# SCH_Latencycam_2024-05-11.net
KiCad netlist of a schematic drawn in EasyEDA
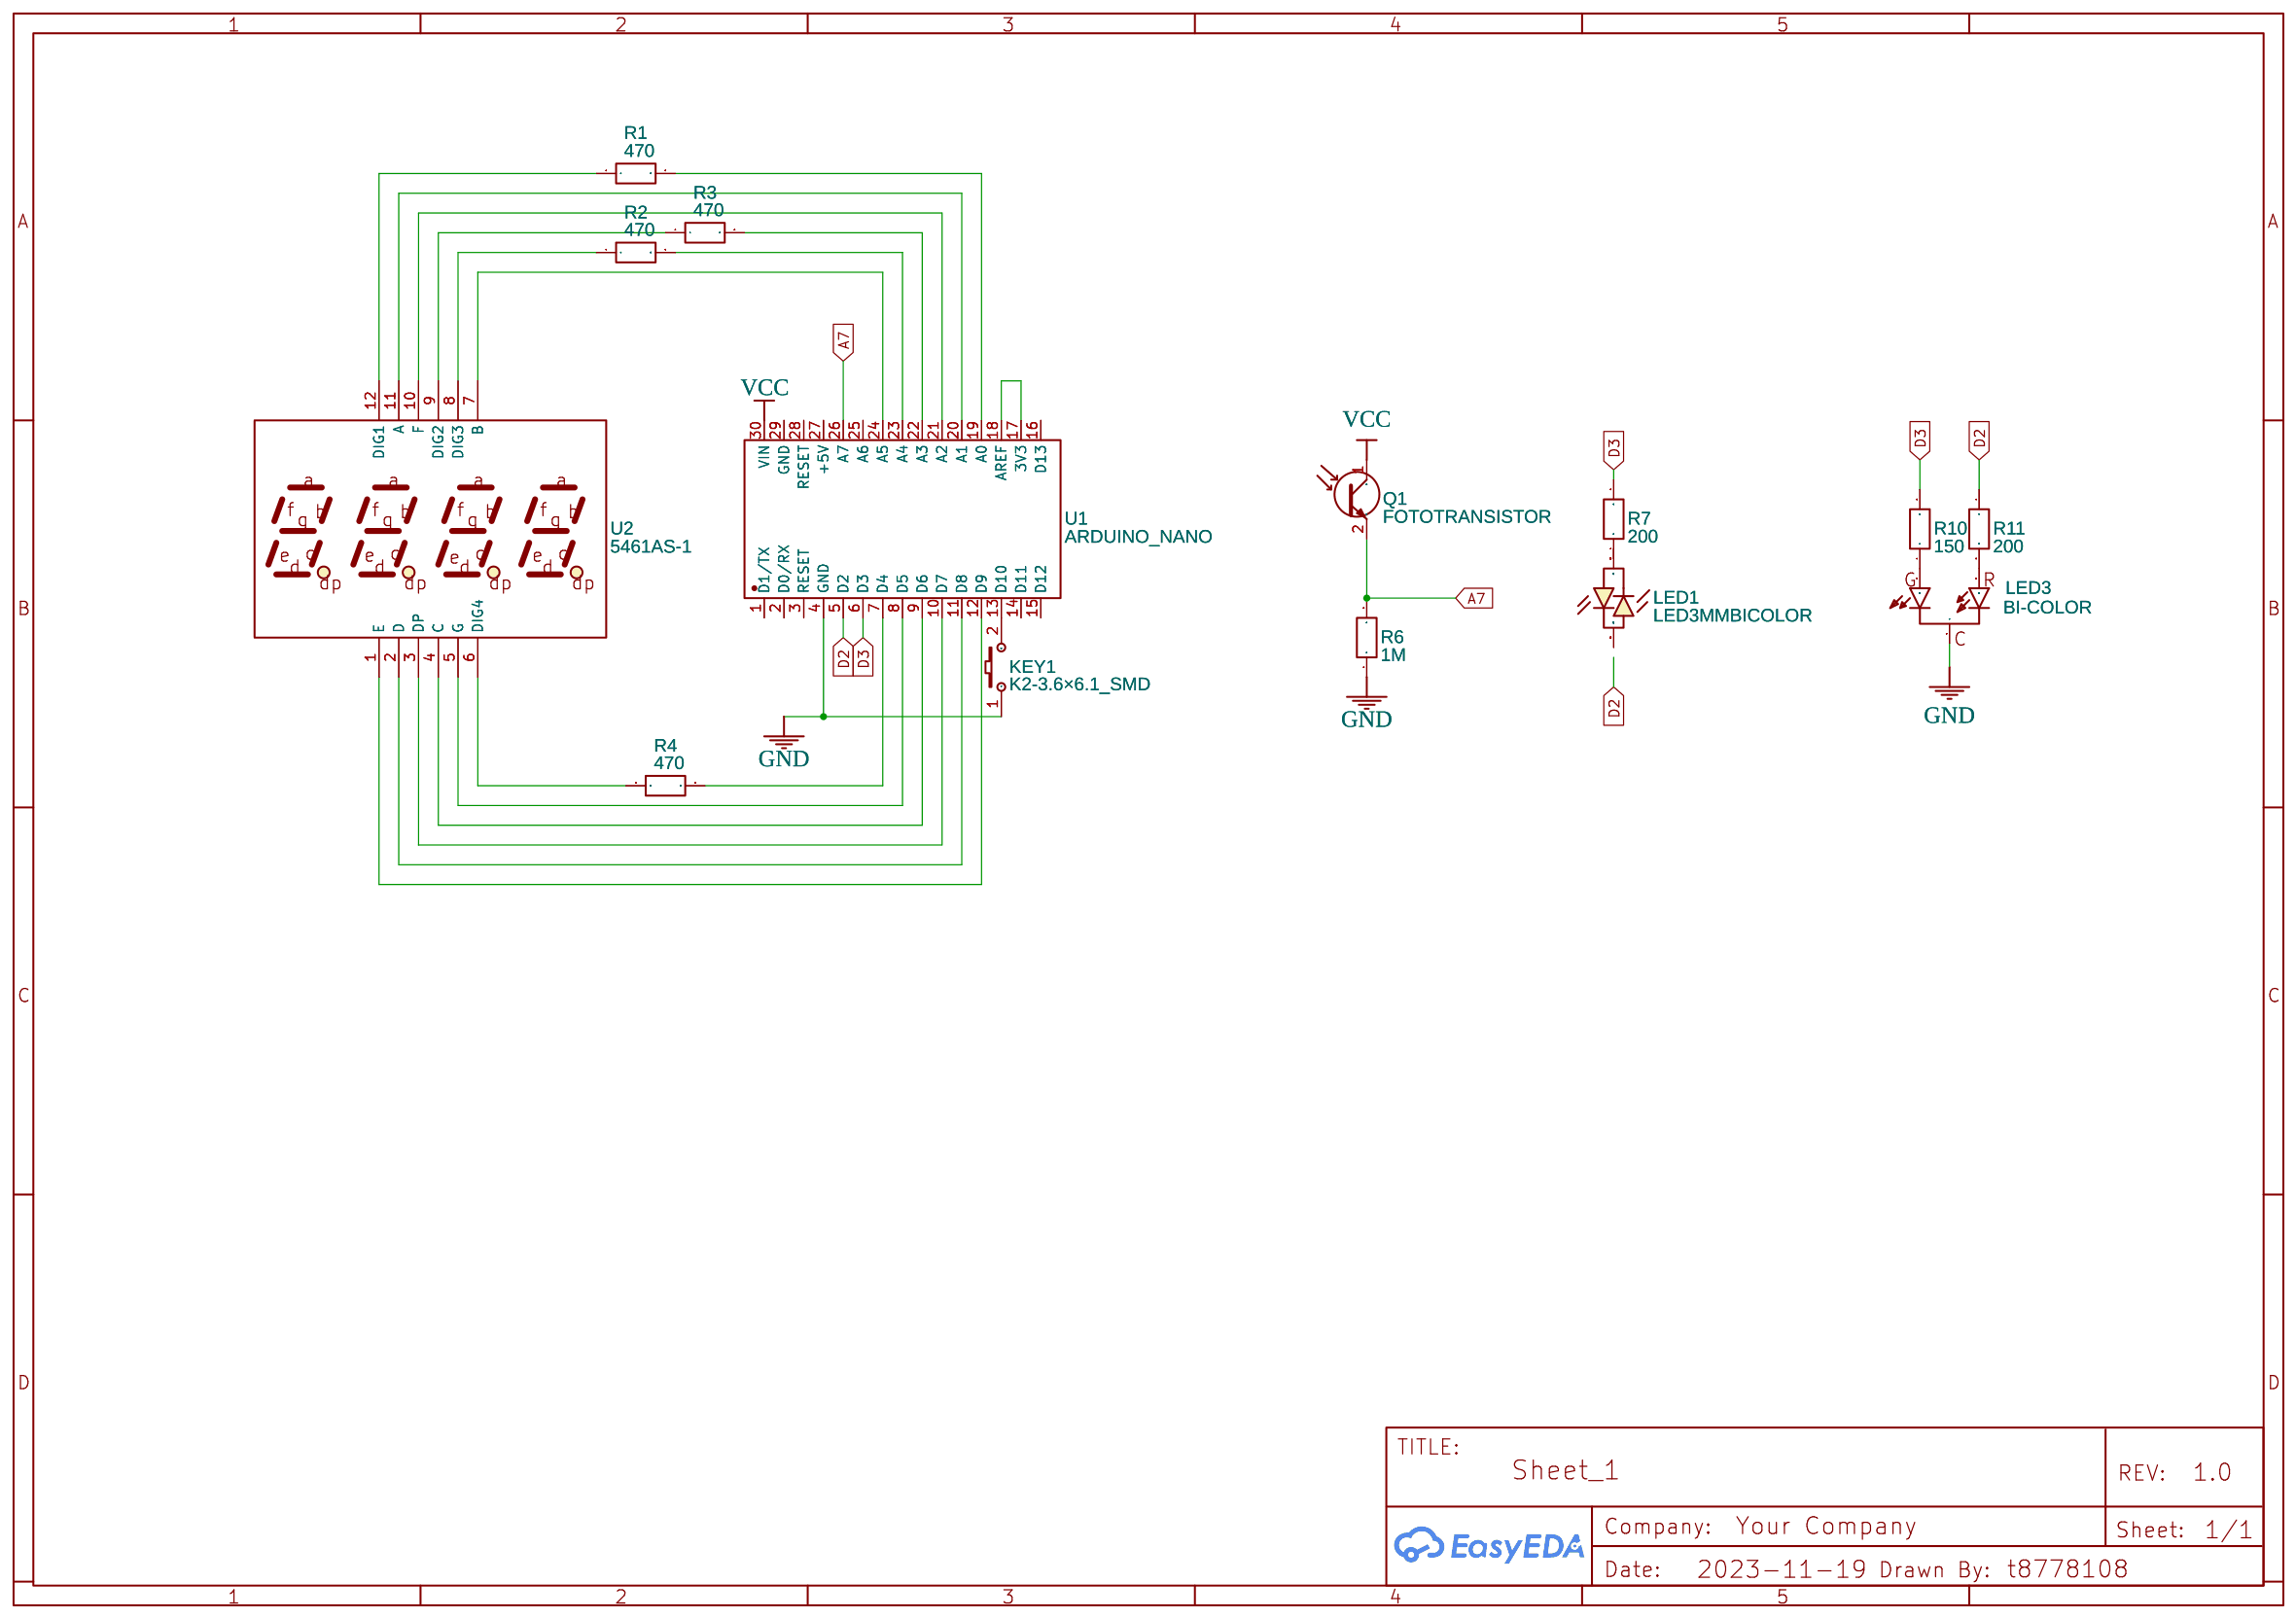
[diagram p0: schematic sheet]

(export (version "E")
  (design (tool "Eeschema 10.0.6"))
  (components
    (comp (ref "KEY1")
      (value "K2-3.6×6.1_SMD")
      (fields (field (name "Manufacturer Part") "K2-1107ST-A4SW-06"))
      (libsource (lib "") (part "K2-3.6×6.1_SMD"))
    )
    (comp (ref "LED1") (value "LED3MMBICOLOR") (libsource (lib "") (part "LED3MMBICOLOR")))
    (comp (ref "LED3") (value "BI-COLOR") (libsource (lib "") (part "BI-COLOR LED 5MM COMMON CATHODE COPY")))
    (comp (ref "Q1") (value "FOTOTRANSISTOR") (libsource (lib "") (part "FOTOTRANSISTOR")))
    (comp (ref "R1") (value "470") (libsource (lib "") (part "R_0603_EU")))
    (comp (ref "R2") (value "470") (libsource (lib "") (part "R_0603_EU")))
    (comp (ref "R3") (value "470") (libsource (lib "") (part "R_0603_EU")))
    (comp (ref "R4") (value "470") (libsource (lib "") (part "R_0603_EU")))
    (comp (ref "R6") (value "1M") (libsource (lib "") (part "R_0603_EU_1")))
    (comp (ref "R7") (value "200") (libsource (lib "") (part "R_0603_EU_1")))
    (comp (ref "R10") (value "150") (libsource (lib "") (part "R_0603_EU_1")))
    (comp (ref "R11") (value "200") (libsource (lib "") (part "R_0603_EU_2")))
    (comp (ref "U1") (value "ARDUINO_NANO") (libsource (lib "") (part "ARDUINO_NANO")))
    (comp (ref "U2") (value "5461AS-1") (libsource (lib "") (part "5461AS-1")))
  )
  (nets
    (net (code "1") (name "A7") (class "Default")
      (node (ref "Q1") (pin "2") (pinfunction "E_2") (pintype "unspecified"))
      (node (ref "R6") (pin "2") (pinfunction "2_2") (pintype "unspecified"))
      (node (ref "U1") (pin "26") (pinfunction "A7_26") (pintype "unspecified"))
    )
    (net (code "2") (name "D2") (class "Default")
      (node (ref "R11") (pin "1") (pinfunction "1_1") (pintype "unspecified"))
      (node (ref "U1") (pin "5") (pinfunction "D2_5") (pintype "unspecified"))
    )
    (net (code "3") (name "D3") (class "Default")
      (node (ref "R10") (pin "2") (pinfunction "2_2") (pintype "unspecified"))
      (node (ref "R7") (pin "2") (pinfunction "2_2") (pintype "unspecified"))
      (node (ref "U1") (pin "6") (pinfunction "D3_6") (pintype "unspecified"))
    )
    (net (code "4") (name "GND") (class "Default")
      (node (ref "KEY1") (pin "1") (pinfunction "1_1") (pintype "unspecified"))
      (node (ref "LED3") (pin "2") (pinfunction "A_2") (pintype "unspecified"))
      (node (ref "R6") (pin "1") (pinfunction "1_1") (pintype "unspecified"))
      (node (ref "U1") (pin "4") (pinfunction "GND_4") (pintype "unspecified"))
    )
    (net (code "5") (name "Net-(LED1-PadAG-CR)") (class "Default")
      (node (ref "LED1") (pin "AG-CR") (pinfunction "AG-CR_AG-CR") (pintype "unspecified"))
      (node (ref "R7") (pin "1") (pinfunction "1_1") (pintype "unspecified"))
    )
    (net (code "6") (name "Net-(LED3-G)") (class "Default")
      (node (ref "LED3") (pin "1") (pinfunction "G_1") (pintype "unspecified"))
      (node (ref "R10") (pin "1") (pinfunction "1_1") (pintype "unspecified"))
    )
    (net (code "7") (name "Net-(LED3-R)") (class "Default")
      (node (ref "LED3") (pin "3") (pinfunction "R_3") (pintype "unspecified"))
      (node (ref "R11") (pin "2") (pinfunction "2_2") (pintype "unspecified"))
    )
    (net (code "8") (name "Net-(U1-3V3)") (class "Default")
      (node (ref "U1") (pin "17") (pinfunction "3V3_17") (pintype "unspecified"))
      (node (ref "U1") (pin "18") (pinfunction "AREF_18") (pintype "unspecified"))
    )
    (net (code "9") (name "Net-(U1-A0)") (class "Default")
      (node (ref "R1") (pin "2") (pinfunction "2_2") (pintype "unspecified"))
      (node (ref "U1") (pin "19") (pinfunction "A0_19") (pintype "unspecified"))
    )
    (net (code "10") (name "Net-(U1-A1)") (class "Default")
      (node (ref "U1") (pin "20") (pinfunction "A1_20") (pintype "unspecified"))
      (node (ref "U2") (pin "11") (pinfunction "A_11") (pintype "input"))
    )
    (net (code "11") (name "Net-(U1-A2)") (class "Default")
      (node (ref "U1") (pin "21") (pinfunction "A2_21") (pintype "unspecified"))
      (node (ref "U2") (pin "10") (pinfunction "F_10") (pintype "input"))
    )
    (net (code "12") (name "Net-(U1-A3)") (class "Default")
      (node (ref "R3") (pin "2") (pinfunction "2_2") (pintype "unspecified"))
      (node (ref "U1") (pin "22") (pinfunction "A3_22") (pintype "unspecified"))
    )
    (net (code "13") (name "Net-(U1-A4)") (class "Default")
      (node (ref "R2") (pin "2") (pinfunction "2_2") (pintype "unspecified"))
      (node (ref "U1") (pin "23") (pinfunction "A4_23") (pintype "unspecified"))
    )
    (net (code "14") (name "Net-(U1-A5)") (class "Default")
      (node (ref "U1") (pin "24") (pinfunction "A5_24") (pintype "unspecified"))
      (node (ref "U2") (pin "7") (pinfunction "B_7") (pintype "input"))
    )
    (net (code "15") (name "Net-(U1-D4)") (class "Default")
      (node (ref "R4") (pin "2") (pinfunction "2_2") (pintype "unspecified"))
      (node (ref "U1") (pin "7") (pinfunction "D4_7") (pintype "unspecified"))
    )
    (net (code "16") (name "Net-(U1-D5)") (class "Default")
      (node (ref "U1") (pin "8") (pinfunction "D5_8") (pintype "unspecified"))
      (node (ref "U2") (pin "5") (pinfunction "G_5") (pintype "input"))
    )
    (net (code "17") (name "Net-(U1-D6)") (class "Default")
      (node (ref "U1") (pin "9") (pinfunction "D6_9") (pintype "unspecified"))
      (node (ref "U2") (pin "4") (pinfunction "C_4") (pintype "input"))
    )
    (net (code "18") (name "Net-(U1-D7)") (class "Default")
      (node (ref "U1") (pin "10") (pinfunction "D7_10") (pintype "unspecified"))
      (node (ref "U2") (pin "3") (pinfunction "DP_3") (pintype "input"))
    )
    (net (code "19") (name "Net-(U1-D8)") (class "Default")
      (node (ref "U1") (pin "11") (pinfunction "D8_11") (pintype "unspecified"))
      (node (ref "U2") (pin "2") (pinfunction "D_2") (pintype "input"))
    )
    (net (code "20") (name "Net-(U1-D9)") (class "Default")
      (node (ref "U1") (pin "12") (pinfunction "D9_12") (pintype "unspecified"))
      (node (ref "U2") (pin "1") (pinfunction "E_1") (pintype "input"))
    )
    (net (code "21") (name "Net-(U1-D10)") (class "Default")
      (node (ref "KEY1") (pin "2") (pinfunction "2_2") (pintype "unspecified"))
      (node (ref "U1") (pin "13") (pinfunction "D10_13") (pintype "unspecified"))
    )
    (net (code "22") (name "Net-(U2-DIG1)") (class "Default")
      (node (ref "R1") (pin "1") (pinfunction "1_1") (pintype "unspecified"))
      (node (ref "U2") (pin "12") (pinfunction "DIG1_12") (pintype "input"))
    )
    (net (code "23") (name "Net-(U2-DIG2)") (class "Default")
      (node (ref "R3") (pin "1") (pinfunction "1_1") (pintype "unspecified"))
      (node (ref "U2") (pin "9") (pinfunction "DIG2_9") (pintype "input"))
    )
    (net (code "24") (name "Net-(U2-DIG3)") (class "Default")
      (node (ref "R2") (pin "1") (pinfunction "1_1") (pintype "unspecified"))
      (node (ref "U2") (pin "8") (pinfunction "DIG3_8") (pintype "input"))
    )
    (net (code "25") (name "Net-(U2-DIG4)") (class "Default")
      (node (ref "R4") (pin "1") (pinfunction "1_1") (pintype "unspecified"))
      (node (ref "U2") (pin "6") (pinfunction "DIG4_6") (pintype "input"))
    )
    (net (code "26") (name "VCC") (class "Default")
      (node (ref "Q1") (pin "1") (pinfunction "C_1") (pintype "unspecified"))
      (node (ref "U1") (pin "30") (pinfunction "VIN_30") (pintype "unspecified"))
    )
    (net (code "27") (name "unconnected-(LED1-PadCG-AR)") (class "Default")
      (node (ref "LED1") (pin "CG-AR") (pinfunction "CG-AR_CG-AR") (pintype "unspecified"))
    )
    (net (code "28") (name "unconnected-(U1-+5V-Pad27)") (class "Default")
      (node (ref "U1") (pin "27") (pinfunction "+5V_27") (pintype "unspecified"))
    )
    (net (code "29") (name "unconnected-(U1-A6-Pad25)") (class "Default")
      (node (ref "U1") (pin "25") (pinfunction "A6_25") (pintype "unspecified"))
    )
    (net (code "30") (name "unconnected-(U1-D0{slash}RX-Pad2)") (class "Default")
      (node (ref "U1") (pin "2") (pinfunction "D0/RX_2") (pintype "unspecified"))
    )
    (net (code "31") (name "unconnected-(U1-D1{slash}TX-Pad1)") (class "Default")
      (node (ref "U1") (pin "1") (pinfunction "D1/TX_1") (pintype "unspecified"))
    )
    (net (code "32") (name "unconnected-(U1-D11-Pad14)") (class "Default")
      (node (ref "U1") (pin "14") (pinfunction "D11_14") (pintype "unspecified"))
    )
    (net (code "33") (name "unconnected-(U1-D12-Pad15)") (class "Default")
      (node (ref "U1") (pin "15") (pinfunction "D12_15") (pintype "unspecified"))
    )
    (net (code "34") (name "unconnected-(U1-D13-Pad16)") (class "Default")
      (node (ref "U1") (pin "16") (pinfunction "D13_16") (pintype "unspecified"))
    )
    (net (code "35") (name "unconnected-(U1-GND-Pad29)") (class "Default")
      (node (ref "U1") (pin "29") (pinfunction "GND_29") (pintype "unspecified"))
    )
    (net (code "36") (name "unconnected-(U1-RESET-Pad3)") (class "Default")
      (node (ref "U1") (pin "3") (pinfunction "RESET_3") (pintype "unspecified"))
    )
    (net (code "37") (name "unconnected-(U1-RESET-Pad28)") (class "Default")
      (node (ref "U1") (pin "28") (pinfunction "RESET_28") (pintype "unspecified"))
    )
  )
)
